# board_RA-02_v2.net
KiCad netlist of a schematic drawn in EAGLE
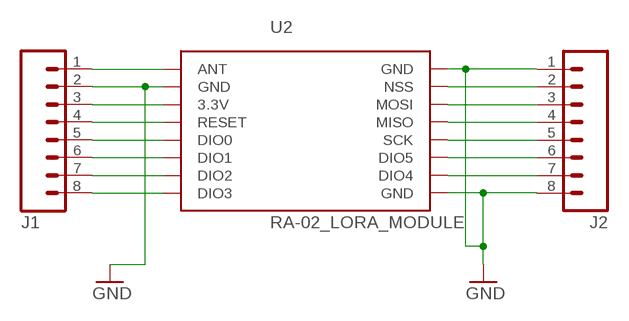
[diagram p0: schematic, sheet 1]

(export (version "E")
  (design (tool "Eeschema 10.0.6"))
  (components
    (comp (ref "J1")
      (value "M08")
      (footprint "eagle-import:1X08_ROUND")
      (libsource (lib "eagle-import") (part "M08"))
    )
    (comp (ref "J2")
      (value "M08")
      (footprint "eagle-import:1X08_ROUND")
      (libsource (lib "eagle-import") (part "M08"))
    )
    (comp (ref "U2")
      (value "RA-02_LORA_MODULE")
      (footprint "eagle-import:RA-02")
      (libsource (lib "eagle-import") (part "RA-02_LORA_MODULE"))
    )
  )
  (nets
    (net (code "1") (name "GND") (class "Default")
      (node (ref "J1") (pin "2") (pinfunction "2_2") (pintype "passive"))
      (node (ref "J2") (pin "1") (pinfunction "1_1") (pintype "passive"))
      (node (ref "J2") (pin "8") (pinfunction "8_8") (pintype "passive"))
      (node (ref "U2") (pin "GND@2") (pinfunction "GND_GND@2") (pintype "power_in"))
      (node (ref "U2") (pin "GND@3") (pinfunction "GND_GND@3") (pintype "power_in"))
      (node (ref "U2") (pin "GND@4") (pinfunction "GND_GND@4") (pintype "power_in"))
    )
    (net (code "2") (name "Net-(J1-Pad1)") (class "Default")
      (node (ref "J1") (pin "1") (pinfunction "1_1") (pintype "passive"))
      (node (ref "U2") (pin "ANT") (pinfunction "ANT_ANT") (pintype "power_in"))
    )
    (net (code "3") (name "Net-(J1-Pad3)") (class "Default")
      (node (ref "J1") (pin "3") (pinfunction "3_3") (pintype "passive"))
      (node (ref "U2") (pin "3.3V") (pinfunction "3.3V_3.3V") (pintype "power_in"))
    )
    (net (code "4") (name "Net-(J1-Pad4)") (class "Default")
      (node (ref "J1") (pin "4") (pinfunction "4_4") (pintype "passive"))
      (node (ref "U2") (pin "RESET") (pinfunction "RESET_RESET") (pintype "bidirectional"))
    )
    (net (code "5") (name "Net-(J1-Pad5)") (class "Default")
      (node (ref "J1") (pin "5") (pinfunction "5_5") (pintype "passive"))
      (node (ref "U2") (pin "DIO0") (pinfunction "DIO0_DIO0") (pintype "bidirectional"))
    )
    (net (code "6") (name "Net-(J1-Pad6)") (class "Default")
      (node (ref "J1") (pin "6") (pinfunction "6_6") (pintype "passive"))
      (node (ref "U2") (pin "DIO1") (pinfunction "DIO1_DIO1") (pintype "bidirectional"))
    )
    (net (code "7") (name "Net-(J1-Pad7)") (class "Default")
      (node (ref "J1") (pin "7") (pinfunction "7_7") (pintype "passive"))
      (node (ref "U2") (pin "DIO2") (pinfunction "DIO2_DIO2") (pintype "bidirectional"))
    )
    (net (code "8") (name "Net-(J1-Pad8)") (class "Default")
      (node (ref "J1") (pin "8") (pinfunction "8_8") (pintype "passive"))
      (node (ref "U2") (pin "DIO3") (pinfunction "DIO3_DIO3") (pintype "bidirectional"))
    )
    (net (code "9") (name "Net-(J2-Pad2)") (class "Default")
      (node (ref "J2") (pin "2") (pinfunction "2_2") (pintype "passive"))
      (node (ref "U2") (pin "NSS") (pinfunction "NSS_NSS") (pintype "bidirectional"))
    )
    (net (code "10") (name "Net-(J2-Pad3)") (class "Default")
      (node (ref "J2") (pin "3") (pinfunction "3_3") (pintype "passive"))
      (node (ref "U2") (pin "MOSI") (pinfunction "MOSI_MOSI") (pintype "bidirectional"))
    )
    (net (code "11") (name "Net-(J2-Pad4)") (class "Default")
      (node (ref "J2") (pin "4") (pinfunction "4_4") (pintype "passive"))
      (node (ref "U2") (pin "MISO") (pinfunction "MISO_MISO") (pintype "bidirectional"))
    )
    (net (code "12") (name "Net-(J2-Pad5)") (class "Default")
      (node (ref "J2") (pin "5") (pinfunction "5_5") (pintype "passive"))
      (node (ref "U2") (pin "SCK") (pinfunction "SCK_SCK") (pintype "bidirectional"))
    )
    (net (code "13") (name "Net-(J2-Pad6)") (class "Default")
      (node (ref "J2") (pin "6") (pinfunction "6_6") (pintype "passive"))
      (node (ref "U2") (pin "DIO5") (pinfunction "DIO5_DIO5") (pintype "bidirectional"))
    )
    (net (code "14") (name "Net-(J2-Pad7)") (class "Default")
      (node (ref "J2") (pin "7") (pinfunction "7_7") (pintype "passive"))
      (node (ref "U2") (pin "DIO4") (pinfunction "DIO4_DIO4") (pintype "bidirectional"))
    )
  )
)
